# Terra_Spray.net
KiCad netlist of a schematic drawn in Altium Designer
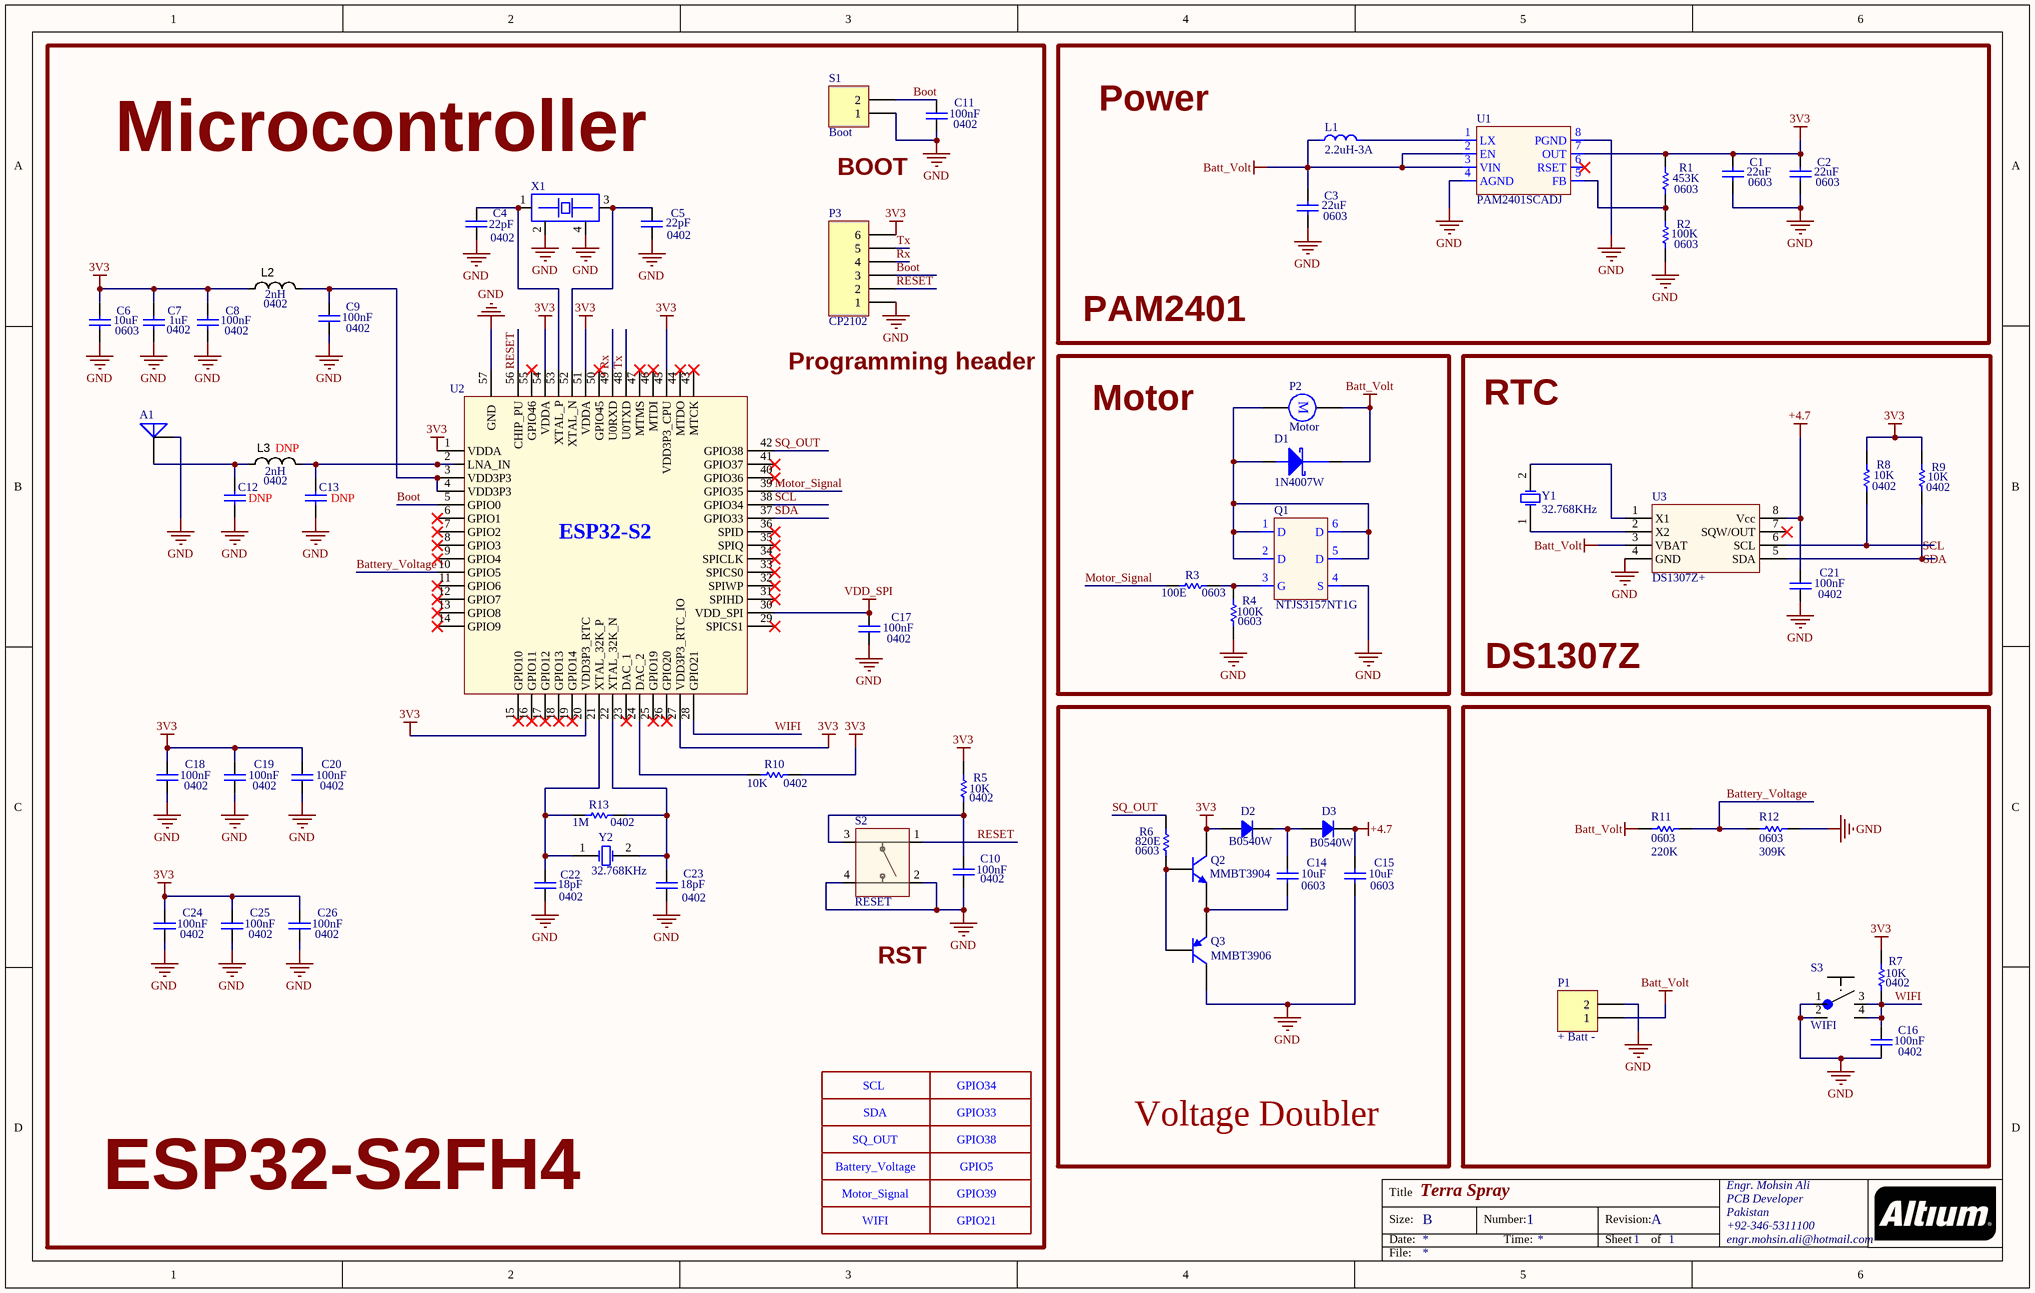
[diagram p0: Terra_Spray.SchDoc]

(export (version "E")
  (design (tool "Eeschema 10.0.6"))
  (components
    (comp (ref "A1")
      (value "Antenna_1")
      (footprint "ESP32 ANT")
      (description "PCB Antenna")
      (fields (field (name "PUBLISHER") "Altium Limited"))
      (libsource (lib "Pd's Sch Lib") (part "Antenna_1"))
    )
    (comp (ref "C1")
      (value "22uF")
      (footprint "CAPC0603")
      (description "Ceramic Capacitor,22uF,0603,6.3V")
      (fields (field (name "CASE/PACKAGE") "0603") (field (name "Comment") "Capacitor"))
      (libsource (lib "Pd's Sch Lib") (part "Capacitor"))
    )
    (comp (ref "C2")
      (value "22uF")
      (footprint "CAPC0603")
      (description "Ceramic Capacitor,22uF,0603,6.3V")
      (fields (field (name "CASE/PACKAGE") "0603") (field (name "Comment") "Capacitor"))
      (libsource (lib "Pd's Sch Lib") (part "Capacitor"))
    )
    (comp (ref "C3")
      (value "22uF")
      (footprint "CAPC0603")
      (description "Ceramic Capacitor,22uF,0603,6.3V")
      (fields (field (name "CASE/PACKAGE") "0603") (field (name "Comment") "Capacitor"))
      (libsource (lib "Pd's Sch Lib") (part "Capacitor"))
    )
    (comp (ref "C4")
      (value "22pF")
      (footprint "capc0402")
      (description "Ceramic Capacitor,22pF,0402,50V")
      (fields (field (name "CASE/PACKAGE") "0402") (field (name "Comment") "Cap"))
      (libsource (lib "CUSTOM TNY290PG") (part "Cap"))
    )
    (comp (ref "C5")
      (value "22pF")
      (footprint "capc0402")
      (description "Ceramic Capacitor,22pF,0402,50V")
      (fields (field (name "CASE/PACKAGE") "0402") (field (name "Comment") "Cap"))
      (libsource (lib "CUSTOM TNY290PG") (part "Cap"))
    )
    (comp (ref "C6")
      (value "10uF")
      (footprint "CAPC0603")
      (description "Ceramic Capacitor,10uF,0603,10V")
      (fields (field (name "CASE/PACKAGE") "0603") (field (name "Comment") "Capacitor"))
      (libsource (lib "Pd's Sch Lib") (part "Capacitor"))
    )
    (comp (ref "C7")
      (value "1uF")
      (footprint "CAPC0402")
      (description "Ceramic Capacitor,1uF,0402,6.3V")
      (fields (field (name "CASE/PACKAGE") "0402") (field (name "Comment") "Capacitor"))
      (libsource (lib "Pd's Sch Lib") (part "Capacitor"))
    )
    (comp (ref "C8")
      (value "100nF")
      (footprint "CAPC0402")
      (description "Ceramic Capacitor,100nF,0402,6.3V")
      (fields (field (name "CASE/PACKAGE") "0402") (field (name "Comment") "Cap"))
      (libsource (lib "Pd's Sch Lib") (part "Capacitor"))
    )
    (comp (ref "C9")
      (value "100nF")
      (footprint "CAPC0402")
      (description "Ceramic Capacitor,100nF,0402,6.3V")
      (fields (field (name "CASE/PACKAGE") "0402") (field (name "Comment") "Cap"))
      (libsource (lib "CUSTOM TNY290PG") (part "Cap"))
    )
    (comp (ref "C10")
      (value "100nF")
      (footprint "CAPC0402")
      (description "Ceramic Capacitor,100nF,0402,6.3V")
      (fields (field (name "CASE/PACKAGE") "0402") (field (name "Comment") "Cap"))
      (libsource (lib "CUSTOM TNY290PG") (part "Cap"))
    )
    (comp (ref "C11")
      (value "100nF")
      (footprint "CAPC0402")
      (description "Ceramic Capacitor,100nF,0402,16V")
      (fields (field (name "CASE/PACKAGE") "0402") (field (name "Comment") "Cap"))
      (libsource (lib "CUSTOM TNY290PG") (part "Cap"))
    )
    (comp (ref "C12")
      (value "Capacitor")
      (footprint "CAPC0402")
      (libsource (lib "Pd's Sch Lib") (part "Capacitor"))
    )
    (comp (ref "C13")
      (value "Capacitor")
      (footprint "CAPC0402")
      (libsource (lib "Pd's Sch Lib") (part "Capacitor"))
    )
    (comp (ref "C14")
      (value "10uF")
      (footprint "CAPC0603")
      (description "Ceramic Capacitor,10uF,0603,10V")
      (fields (field (name "CASE/PACKAGE") "0603") (field (name "Comment") "Capacitor"))
      (libsource (lib "") (part "Capacitor_1"))
    )
    (comp (ref "C15")
      (value "10uF")
      (footprint "CAPC0603")
      (description "Ceramic Capacitor,10uF,0603,10V")
      (fields (field (name "CASE/PACKAGE") "0603") (field (name "Comment") "Capacitor"))
      (libsource (lib "") (part "Capacitor_1"))
    )
    (comp (ref "C16")
      (value "100nF")
      (footprint "CAPC0402")
      (description "Ceramic Capacitor,100nF,0402,6.3\r\nV")
      (fields (field (name "CASE/PACKAGE") "0402") (field (name "Comment") "Cap"))
      (libsource (lib "CUSTOM TNY290PG") (part "Cap"))
    )
    (comp (ref "C17")
      (value "100nF")
      (footprint "CAPC0402")
      (description "Ceramic Capacitor,100nF,0402,6.3V")
      (fields (field (name "CASE/PACKAGE") "0402") (field (name "Comment") "Cap"))
      (libsource (lib "CUSTOM TNY290PG") (part "Cap"))
    )
    (comp (ref "C18")
      (value "100nF")
      (footprint "CAPC0402")
      (description "Ceramic Capacitor,100nF,0402,6.3V")
      (fields (field (name "CASE/PACKAGE") "0402") (field (name "Comment") "Cap"))
      (libsource (lib "CUSTOM TNY290PG") (part "Cap"))
    )
    (comp (ref "C19")
      (value "100nF")
      (footprint "CAPC0402")
      (description "Ceramic Capacitor,100nF,0402,6.3V")
      (fields (field (name "CASE/PACKAGE") "0402") (field (name "Comment") "Cap"))
      (libsource (lib "CUSTOM TNY290PG") (part "Cap"))
    )
    (comp (ref "C20")
      (value "100nF")
      (footprint "CAPC0402")
      (description "Ceramic Capacitor,100nF,0402,6.3V")
      (fields (field (name "CASE/PACKAGE") "0402") (field (name "Comment") "Cap"))
      (libsource (lib "CUSTOM TNY290PG") (part "Cap"))
    )
    (comp (ref "C21")
      (value "100nF")
      (footprint "CAPC0402")
      (description "Ceramic Capacitor,100nF,0402,6.3\r\nV")
      (fields (field (name "CASE/PACKAGE") "0402") (field (name "Comment") "Cap"))
      (libsource (lib "CUSTOM TNY290PG") (part "Cap"))
    )
    (comp (ref "C22")
      (value "18pF")
      (footprint "capc0402")
      (description "Ceramic Capacitor,18pF,0402,50V")
      (fields (field (name "CASE/PACKAGE") "0402") (field (name "Comment") "Cap"))
      (libsource (lib "CUSTOM TNY290PG") (part "Cap"))
    )
    (comp (ref "C23")
      (value "18pF")
      (footprint "capc0402")
      (description "Ceramic Capacitor,18pF,0402,50V")
      (fields (field (name "CASE/PACKAGE") "0402") (field (name "Comment") "Cap"))
      (libsource (lib "CUSTOM TNY290PG") (part "Cap"))
    )
    (comp (ref "C24")
      (value "100nF")
      (footprint "CAPC0402")
      (description "Ceramic Capacitor,100nF,0402,6.3V")
      (fields (field (name "CASE/PACKAGE") "0402") (field (name "Comment") "Cap"))
      (libsource (lib "CUSTOM TNY290PG") (part "Cap"))
    )
    (comp (ref "C25")
      (value "100nF")
      (footprint "CAPC0402")
      (description "Ceramic Capacitor,100nF,0402,6.3V")
      (fields (field (name "CASE/PACKAGE") "0402") (field (name "Comment") "Cap"))
      (libsource (lib "CUSTOM TNY290PG") (part "Cap"))
    )
    (comp (ref "C26")
      (value "100nF")
      (footprint "CAPC0402")
      (description "Ceramic Capacitor,100nF,0402,6.3V")
      (fields (field (name "CASE/PACKAGE") "0402") (field (name "Comment") "Cap"))
      (libsource (lib "CUSTOM TNY290PG") (part "Cap"))
    )
    (comp (ref "D1")
      (value "1N4007W")
      (footprint "SOD-123")
      (description "Rectifiers RECTIFIER DIODE 1A 1000V")
      (fields (field (name "PART NO") "CGRM4007-G"))
      (libsource (lib "Integrated_Library_FEDEVEL_APR_2015") (part "BAT54HT1G"))
    )
    (comp (ref "D2")
      (value "B0540W")
      (footprint "SOD123 - duplicate")
      (description "Diode Schottky 40V 0.5A 2-Pin SOD-123 T/R")
      (libsource (lib "Pd's Sch Lib") (part "Diode"))
    )
    (comp (ref "D3")
      (value "B0540W")
      (footprint "SOD123 - duplicate")
      (description "Diode Schottky 40V 0.5A 2-Pin SOD-123 T/R")
      (libsource (lib "Pd's Sch Lib") (part "Diode"))
    )
    (comp (ref "L1")
      (value "2.2uH-3A")
      (footprint "INDP5050X20N")
      (fields (field (name "TOLERANCE") "30%") (field (name "Comment") "Inductor"))
      (libsource (lib "Inductors") (part "74404052022"))
    )
    (comp (ref "L2")
      (value "Inductor")
      (footprint "inductor 0402")
      (description "2nH ±0.3nH 900mA 120mΩ 0402 Inductors (SMD) RoHS")
      (fields
        (field (name "MANUFACTURER PART NUMBER") "LQG15HN2N0S02D")
        (field (name "CASE/PACKAGE") "0402")
        (field (name "INDUCTANCE") "2nH")
      )
      (libsource (lib "Pd's Sch Lib") (part "Inductor"))
    )
    (comp (ref "L3")
      (value "Inductor")
      (footprint "inductor 0402")
      (description "2nH ±0.3nH 900mA 120mΩ 0402 Inductors (SMD) RoHS")
      (fields
        (field (name "MANUFACTURER PART NUMBER") "LQG15HN2N0S02D")
        (field (name "CASE CODE (IMPERIAL)") "0402")
        (field (name "INDUCTANCE") "2nH")
      )
      (libsource (lib "Pd's Sch Lib") (part "Inductor"))
    )
    (comp (ref "P1")
      (value "+ Batt -")
      (footprint "2 pin 2.5mm - Header")
      (description "Header, 2-Pin")
      (fields (field (name "PUBLISHER") "Altium Limited"))
      (libsource (lib "Miscellaneous Connectors") (part "Header 2"))
    )
    (comp (ref "P2")
      (value "Motor")
      (footprint "2 pin 2.5mm - Header")
      (description "Motor, General Kind")
      (fields (field (name "PUBLISHER") "Altium Limited"))
      (libsource (lib "Miscellaneous Devices") (part "Motor"))
    )
    (comp (ref "P3")
      (value "CP2102")
      (footprint "Header 6x1")
      (description "Header, 6-Pin")
      (fields (field (name "PUBLISHER") "Altium Limited"))
      (libsource (lib "Miscellaneous Connectors") (part "Header 6"))
    )
    (comp (ref "Q1")
      (value "Mosfet")
      (footprint "SOT-363")
      (description "N-Channel 20V 3.2A (Ta) 1W (Ta) Surface Mount SC-88/SC70-6/SOT-363")
      (fields (field (name "PART NO") "NTJS3157NT1G"))
      (libsource (lib "Terra_Spray") (part "NTJS3157NT1G"))
    )
    (comp (ref "Q2")
      (value "NPN BJT Transistor")
      (footprint "SOT-23")
      (description "Bipolar Transistors - BJT SOT-23 NPN")
      (fields (field (name "MANUFACTURER PART NUMBER") "MMBT3904"))
      (libsource (lib "Pd's Sch Lib") (part "NPN BJT Transistor"))
    )
    (comp (ref "Q3")
      (value "PNP BJT Transistor")
      (footprint "SOT-23")
      (fields
        (field (name "MANUFACTURER") "ON Semiconductor")
        (field (name "MANUFACTURER PART NUMBER") "MMBT3906")
      )
      (libsource (lib "Pd's Sch Lib") (part "PNP BJT Transistor"))
    )
    (comp (ref "R1")
      (value "453K")
      (footprint "RESC0603")
      (description "Thick Film Resistor -  453Kohm, 1%, 0603")
      (fields (field (name "CASE/PACKAGE") "0603") (field (name "Comment") "Resistor"))
      (libsource (lib "Pd's Sch Lib") (part "Resistor"))
    )
    (comp (ref "R2")
      (value "100K")
      (footprint "RESC0603")
      (description "Thick Film Resistor -  100Kohm, 1%, 0603")
      (fields (field (name "CASE/PACKAGE") "0603") (field (name "Comment") "Resistor"))
      (libsource (lib "Pd's Sch Lib") (part "Resistor"))
    )
    (comp (ref "R3")
      (value "100E")
      (footprint "RESC0603")
      (description "Thick Film Resistor -  100ohm, 1%, 0603")
      (fields (field (name "CASE/PACKAGE") "0603") (field (name "Comment") "Resistor"))
      (libsource (lib "Pd's Sch Lib") (part "Resistor"))
    )
    (comp (ref "R4")
      (value "100K")
      (footprint "RESC0603")
      (description "Thick Film Resistor -  100Kohm, 1%, 0603")
      (fields (field (name "CASE/PACKAGE") "0603") (field (name "Comment") "Resistor"))
      (libsource (lib "Pd's Sch Lib") (part "Resistor"))
    )
    (comp (ref "R5")
      (value "10K")
      (footprint "RESC0402")
      (description "Thick Film Resistor -  10Kohm, 1%, 0402")
      (fields (field (name "CASE/PACKAGE") "0402") (field (name "Comment") "Resistor"))
      (libsource (lib "Pd's Sch Lib") (part "Resistor"))
    )
    (comp (ref "R6")
      (value "820E")
      (footprint "RESC0603")
      (description "Thick Film Resistor -  820ohm, 1%, 0603")
      (fields (field (name "CASE/PACKAGE") "0603") (field (name "Comment") "Resistor"))
      (libsource (lib "Pd's Sch Lib") (part "Resistor"))
    )
    (comp (ref "R7")
      (value "10K")
      (footprint "RESC0402")
      (description "Thick Film Resistor -  10Kohm, 1%, 0402")
      (fields (field (name "CASE/PACKAGE") "0402") (field (name "Comment") "Resistor"))
      (libsource (lib "Pd's Sch Lib") (part "Resistor"))
    )
    (comp (ref "R8")
      (value "10K")
      (footprint "RESC0402")
      (description "Thick Film Resistor -  10Kohm, 1%, 0402")
      (fields (field (name "CASE/PACKAGE") "0402") (field (name "Comment") "Resistor"))
      (libsource (lib "Pd's Sch Lib") (part "Resistor"))
    )
    (comp (ref "R9")
      (value "10K")
      (footprint "RESC0402")
      (description "Thick Film Resistor -  10Kohm, 1%, 0402")
      (fields (field (name "CASE/PACKAGE") "0402") (field (name "Comment") "Resistor"))
      (libsource (lib "Pd's Sch Lib") (part "Resistor"))
    )
    (comp (ref "R10")
      (value "10K")
      (footprint "RESC0402")
      (description "Thick Film Resistor -  10Kohm, 1%, 0402")
      (fields (field (name "CASE/PACKAGE") "0402") (field (name "Comment") "Resistor"))
      (libsource (lib "Pd's Sch Lib") (part "Resistor"))
    )
    (comp (ref "R11")
      (value "220K")
      (footprint "RESC0603")
      (description "Thick Film Resistor -  220Kohm, 1%, 0603")
      (fields (field (name "CASE/PACKAGE") "0603") (field (name "Comment") "Resistor"))
      (libsource (lib "Pd's Sch Lib") (part "Resistor"))
    )
    (comp (ref "R12")
      (value "309K")
      (footprint "RESC0603")
      (description "Thick Film Resistor -  309Kohm, 1%, 0603")
      (fields (field (name "CASE/PACKAGE") "0603") (field (name "Comment") "Resistor"))
      (libsource (lib "Pd's Sch Lib") (part "Resistor"))
    )
    (comp (ref "R13")
      (value "1M")
      (footprint "RESC0402")
      (description "Thick Film Resistor -  1Mohm, 1%, 0402")
      (fields (field (name "CASE/PACKAGE") "0402") (field (name "Comment") "Resistor"))
      (libsource (lib "Pd's Sch Lib") (part "Resistor"))
    )
    (comp (ref "S1")
      (value "Boot")
      (footprint "Switch Replacement")
      (description "Header, 2-Pin")
      (fields (field (name "PUBLISHER") "Altium Limited"))
      (libsource (lib "Miscellaneous Connectors") (part "Header 2"))
    )
    (comp (ref "S2")
      (value "RESET")
      (footprint "434153017835")
      (description "SWITCH TACTILE SPST-NO 0.05A 12V")
      (fields (field (name "MANUFACTURER") "Wurth Electronics") (field (name "Comment") "Button"))
      (libsource (lib "Buttons") (part "434153017835"))
    )
    (comp (ref "S3")
      (value "WIFI")
      (footprint "FSMJ - SMD - Wifi")
      (description "Pushbutton 6x6mm, Actuator Height off PCB, Vertical 9.50mm")
      (fields (field (name "MF") "TE Connectivity") (field (name "MP") "FSM14J"))
      (libsource (lib "Main_PCB") (part "FSM14J"))
    )
    (comp (ref "U1")
      (value "PAM2401SCADJ")
      (footprint "8-TSSOP, 8-MSOP")
      (description "IC REG BOOST ADJ 3A SYNC 8MSOP")
      (libsource (lib "Regulators") (part "PAM2401SCADJ"))
    )
    (comp (ref "U2")
      (value "ESP32-S2")
      (footprint "QFN56-7x7mm")
      (description "WiFi 802.11b/g/n Transceiver Module 2.4GHz")
      (fields (field (name "MANUFACTURER PART NUMBER") "ESP32-S2FH4"))
      (libsource (lib "Pd's Sch Lib") (part "ESP32-S2"))
    )
    (comp (ref "U3")
      (value "DS1307Z+")
      (footprint "SOIC-8")
      (description "SERIAL TIME CHIP 8PIN, SOIC")
      (fields (field (name "VOLTAGE") "5V"))
      (libsource (lib "IC's") (part "DS1307Z+"))
    )
    (comp (ref "X1")
      (value "CRYSTAL_1")
      (footprint "Crystal_3225")
      (description "40MHz ±10ppm 10pF 30Ω SMD-3225 SMD Crystal Resonators RoHS")
      (fields (field (name "MANUFACTURER PART NUMBER") "7M40000049"))
      (libsource (lib "Pd's Sch Lib") (part "CRYSTAL_1_1"))
    )
    (comp (ref "Y1")
      (value "32.768KHz")
      (footprint "32.728Khz")
      (description "Crystal Oscillator")
      (fields (field (name "PUBLISHER") "Altium Limited"))
      (libsource (lib "Miscellaneous Devices") (part "XTAL"))
    )
    (comp (ref "Y2")
      (value "32.768KHz")
      (footprint "32.728Khz")
      (description "Crystal Oscillator")
      (fields (field (name "PUBLISHER") "Altium Limited"))
      (libsource (lib "Miscellaneous Devices") (part "XTAL"))
    )
  )
  (nets
    (net (code "1") (name "+4.7") (class "Default")
      (node (ref "C15") (pin "1") (pinfunction "1_1") (pintype "passive"))
      (node (ref "C21") (pin "1") (pinfunction "1_1") (pintype "passive"))
      (node (ref "D3") (pin "K") (pinfunction "K_K") (pintype "passive"))
      (node (ref "U3") (pin "8") (pinfunction "Vcc_8") (pintype "passive"))
    )
    (net (code "2") (name "/Battery_Voltage") (class "Default")
      (node (ref "R11") (pin "1") (pinfunction "1_1") (pintype "passive"))
      (node (ref "R12") (pin "2") (pinfunction "2_2") (pintype "passive"))
      (node (ref "U2") (pin "10") (pinfunction "GPIO5_10") (pintype "passive"))
    )
    (net (code "3") (name "/Boot") (class "Default")
      (node (ref "C11") (pin "2") (pinfunction "2_2") (pintype "passive"))
      (node (ref "P3") (pin "3") (pinfunction "3_3") (pintype "passive"))
      (node (ref "S1") (pin "2") (pinfunction "2_2") (pintype "passive"))
      (node (ref "U2") (pin "5") (pinfunction "GPIO0_5") (pintype "passive"))
    )
    (net (code "10") (name "/Motor_Signal") (class "Default")
      (node (ref "R3") (pin "2") (pinfunction "2_2") (pintype "passive"))
      (node (ref "U2") (pin "39") (pinfunction "GPIO35_39") (pintype "passive"))
    )
    (net (code "11") (name "/RESET") (class "Default")
      (node (ref "P3") (pin "2") (pinfunction "2_2") (pintype "passive"))
      (node (ref "S2") (pin "1") (pinfunction "1_1") (pintype "passive"))
      (node (ref "U2") (pin "56") (pinfunction "CHIP_PU_56") (pintype "passive"))
    )
    (net (code "12") (name "/Rx") (class "Default")
      (node (ref "P3") (pin "4") (pinfunction "4_4") (pintype "passive"))
      (node (ref "U2") (pin "49") (pinfunction "U0RXD_49") (pintype "passive"))
    )
    (net (code "13") (name "/SCL") (class "Default")
      (node (ref "R8") (pin "1") (pinfunction "1_1") (pintype "passive"))
      (node (ref "U2") (pin "38") (pinfunction "GPIO34_38") (pintype "passive"))
      (node (ref "U3") (pin "6") (pinfunction "SCL_6") (pintype "passive"))
    )
    (net (code "14") (name "/SDA") (class "Default")
      (node (ref "R9") (pin "1") (pinfunction "1_1") (pintype "passive"))
      (node (ref "U2") (pin "37") (pinfunction "GPIO33_37") (pintype "passive"))
      (node (ref "U3") (pin "5") (pinfunction "SDA_5") (pintype "passive"))
    )
    (net (code "15") (name "/SQ_OUT") (class "Default")
      (node (ref "R6") (pin "2") (pinfunction "2_2") (pintype "passive"))
      (node (ref "U2") (pin "42") (pinfunction "GPIO38_42") (pintype "passive"))
    )
    (net (code "16") (name "/Tx") (class "Default")
      (node (ref "P3") (pin "5") (pinfunction "5_5") (pintype "passive"))
      (node (ref "U2") (pin "48") (pinfunction "U0TXD_48") (pintype "passive"))
    )
    (net (code "17") (name "/WIFI") (class "Default")
      (node (ref "C16") (pin "2") (pinfunction "2_2") (pintype "passive"))
      (node (ref "R7") (pin "1") (pinfunction "1_1") (pintype "passive"))
      (node (ref "S3") (pin "3") (pinfunction "2_3") (pintype "passive"))
      (node (ref "S3") (pin "4") (pinfunction "2_4") (pintype "passive"))
      (node (ref "U2") (pin "28") (pinfunction "GPIO21_28") (pintype "passive"))
    )
    (net (code "18") (name "3V3") (class "Default")
      (node (ref "C1") (pin "2") (pinfunction "2_2") (pintype "passive"))
      (node (ref "C18") (pin "1") (pinfunction "1_1") (pintype "passive"))
      (node (ref "C19") (pin "1") (pinfunction "1_1") (pintype "passive"))
      (node (ref "C2") (pin "2") (pinfunction "2_2") (pintype "passive"))
      (node (ref "C20") (pin "1") (pinfunction "1_1") (pintype "passive"))
      (node (ref "C24") (pin "1") (pinfunction "1_1") (pintype "passive"))
      (node (ref "C25") (pin "1") (pinfunction "1_1") (pintype "passive"))
      (node (ref "C26") (pin "1") (pinfunction "1_1") (pintype "passive"))
      (node (ref "C6") (pin "2") (pinfunction "2_2") (pintype "passive"))
      (node (ref "C7") (pin "2") (pinfunction "2_2") (pintype "passive"))
      (node (ref "C8") (pin "2") (pinfunction "2_2") (pintype "passive"))
      (node (ref "D2") (pin "A") (pinfunction "A_A") (pintype "passive"))
      (node (ref "L2") (pin "1") (pinfunction "1_1") (pintype "passive"))
      (node (ref "P3") (pin "6") (pinfunction "6_6") (pintype "passive"))
      (node (ref "Q2") (pin "3") (pinfunction "C_3") (pintype "passive"))
      (node (ref "R1") (pin "2") (pinfunction "2_2") (pintype "passive"))
      (node (ref "R10") (pin "1") (pinfunction "1_1") (pintype "passive"))
      (node (ref "R5") (pin "2") (pinfunction "2_2") (pintype "passive"))
      (node (ref "R7") (pin "2") (pinfunction "2_2") (pintype "passive"))
      (node (ref "R8") (pin "2") (pinfunction "2_2") (pintype "passive"))
      (node (ref "R9") (pin "2") (pinfunction "2_2") (pintype "passive"))
      (node (ref "U1") (pin "7") (pinfunction "OUT_7") (pintype "passive"))
      (node (ref "U2") (pin "1") (pinfunction "VDDA_1") (pintype "passive"))
      (node (ref "U2") (pin "20") (pinfunction "VDD3P3_RTC_20") (pintype "passive"))
      (node (ref "U2") (pin "27") (pinfunction "VDD3P3_RTC_IO_27") (pintype "passive"))
      (node (ref "U2") (pin "45") (pinfunction "VDD3P3_CPU_45") (pintype "passive"))
      (node (ref "U2") (pin "51") (pinfunction "VDDA_51") (pintype "passive"))
      (node (ref "U2") (pin "54") (pinfunction "VDDA_54") (pintype "passive"))
    )
    (net (code "19") (name "Batt_Volt") (class "Default")
      (node (ref "C3") (pin "2") (pinfunction "2_2") (pintype "passive"))
      (node (ref "D1") (pin "1") (pinfunction "Cathode_1") (pintype "passive"))
      (node (ref "L1") (pin "1") (pinfunction "1_1") (pintype "passive"))
      (node (ref "P1") (pin "1") (pinfunction "1_1") (pintype "passive"))
      (node (ref "P2") (pin "1") (pinfunction "1_1") (pintype "passive"))
      (node (ref "R11") (pin "2") (pinfunction "2_2") (pintype "passive"))
      (node (ref "U1") (pin "2") (pinfunction "EN_2") (pintype "passive"))
      (node (ref "U1") (pin "3") (pinfunction "VIN_3") (pintype "passive"))
      (node (ref "U3") (pin "3") (pinfunction "VBAT_3") (pintype "passive"))
    )
    (net (code "20") (name "GND") (class "Default")
      (node (ref "A1") (pin "2") (pinfunction "GND_2") (pintype "passive"))
      (node (ref "C1") (pin "1") (pinfunction "1_1") (pintype "passive"))
      (node (ref "C10") (pin "2") (pinfunction "2_2") (pintype "passive"))
      (node (ref "C11") (pin "1") (pinfunction "1_1") (pintype "passive"))
      (node (ref "C12") (pin "1") (pinfunction "1_1") (pintype "passive"))
      (node (ref "C13") (pin "1") (pinfunction "1_1") (pintype "passive"))
      (node (ref "C15") (pin "2") (pinfunction "2_2") (pintype "passive"))
      (node (ref "C16") (pin "1") (pinfunction "1_1") (pintype "passive"))
      (node (ref "C17") (pin "2") (pinfunction "2_2") (pintype "passive"))
      (node (ref "C18") (pin "2") (pinfunction "2_2") (pintype "passive"))
      (node (ref "C19") (pin "2") (pinfunction "2_2") (pintype "passive"))
      (node (ref "C2") (pin "1") (pinfunction "1_1") (pintype "passive"))
      (node (ref "C20") (pin "2") (pinfunction "2_2") (pintype "passive"))
      (node (ref "C21") (pin "2") (pinfunction "2_2") (pintype "passive"))
      (node (ref "C22") (pin "1") (pinfunction "1_1") (pintype "passive"))
      (node (ref "C23") (pin "1") (pinfunction "1_1") (pintype "passive"))
      (node (ref "C24") (pin "2") (pinfunction "2_2") (pintype "passive"))
      (node (ref "C25") (pin "2") (pinfunction "2_2") (pintype "passive"))
      (node (ref "C26") (pin "2") (pinfunction "2_2") (pintype "passive"))
      (node (ref "C3") (pin "1") (pinfunction "1_1") (pintype "passive"))
      (node (ref "C4") (pin "1") (pinfunction "1_1") (pintype "passive"))
      (node (ref "C5") (pin "1") (pinfunction "1_1") (pintype "passive"))
      (node (ref "C6") (pin "1") (pinfunction "1_1") (pintype "passive"))
      (node (ref "C7") (pin "1") (pinfunction "1_1") (pintype "passive"))
      (node (ref "C8") (pin "1") (pinfunction "1_1") (pintype "passive"))
      (node (ref "C9") (pin "2") (pinfunction "2_2") (pintype "passive"))
      (node (ref "P1") (pin "2") (pinfunction "2_2") (pintype "passive"))
      (node (ref "P3") (pin "1") (pinfunction "1_1") (pintype "passive"))
      (node (ref "Q1") (pin "4") (pinfunction "S_4") (pintype "passive"))
      (node (ref "Q3") (pin "3") (pinfunction "C_3") (pintype "passive"))
      (node (ref "R12") (pin "1") (pinfunction "1_1") (pintype "passive"))
      (node (ref "R2") (pin "2") (pinfunction "2_2") (pintype "passive"))
      (node (ref "R4") (pin "2") (pinfunction "2_2") (pintype "passive"))
      (node (ref "S1") (pin "1") (pinfunction "1_1") (pintype "passive"))
      (node (ref "S2") (pin "2") (pinfunction "2_2") (pintype "passive"))
      (node (ref "S2") (pin "4") (pinfunction "4_4") (pintype "passive"))
      (node (ref "S3") (pin "1") (pinfunction "1_1") (pintype "passive"))
      (node (ref "S3") (pin "2") (pinfunction "1_2") (pintype "passive"))
      (node (ref "U1") (pin "4") (pinfunction "AGND_4") (pintype "passive"))
      (node (ref "U1") (pin "8") (pinfunction "PGND_8") (pintype "passive"))
      (node (ref "U2") (pin "57") (pinfunction "GND_57") (pintype "passive"))
      (node (ref "U3") (pin "4") (pinfunction "GND_4") (pintype "passive"))
      (node (ref "X1") (pin "2") (pinfunction "2_2") (pintype "passive"))
      (node (ref "X1") (pin "4") (pinfunction "4_4") (pintype "passive"))
    )
    (net (code "21") (name "Net-(A1-ANT)") (class "Default")
      (node (ref "A1") (pin "1") (pinfunction "ANT_1") (pintype "passive"))
      (node (ref "C12") (pin "2") (pinfunction "2_2") (pintype "passive"))
      (node (ref "L3") (pin "1") (pinfunction "1_1") (pintype "passive"))
    )
    (net (code "22") (name "Net-(C9-Pad1)") (class "Default")
      (node (ref "C9") (pin "1") (pinfunction "1_1") (pintype "passive"))
      (node (ref "L2") (pin "2") (pinfunction "2_2") (pintype "passive"))
      (node (ref "U2") (pin "3") (pinfunction "VDD3P3_3") (pintype "passive"))
      (node (ref "U2") (pin "4") (pinfunction "VDD3P3_4") (pintype "passive"))
    )
    (net (code "23") (name "Net-(C10-Pad1)") (class "Default")
      (node (ref "C10") (pin "1") (pinfunction "1_1") (pintype "passive"))
      (node (ref "R5") (pin "1") (pinfunction "1_1") (pintype "passive"))
      (node (ref "S2") (pin "3") (pinfunction "3_3") (pintype "passive"))
    )
    (net (code "24") (name "Net-(C14-Pad1)") (class "Default")
      (node (ref "C14") (pin "1") (pinfunction "1_1") (pintype "passive"))
      (node (ref "D2") (pin "K") (pinfunction "K_K") (pintype "passive"))
      (node (ref "D3") (pin "A") (pinfunction "A_A") (pintype "passive"))
    )
    (net (code "25") (name "Net-(D1-Anode)") (class "Default")
      (node (ref "D1") (pin "2") (pinfunction "Anode_2") (pintype "passive"))
      (node (ref "P2") (pin "2") (pinfunction "2_2") (pintype "passive"))
      (node (ref "Q1") (pin "1") (pinfunction "D_1") (pintype "passive"))
      (node (ref "Q1") (pin "2") (pinfunction "D_2") (pintype "passive"))
      (node (ref "Q1") (pin "5") (pinfunction "D_5") (pintype "passive"))
      (node (ref "Q1") (pin "6") (pinfunction "D_6") (pintype "passive"))
    )
    (net (code "26") (name "Net-(Q1-G)") (class "Default")
      (node (ref "Q1") (pin "3") (pinfunction "G_3") (pintype "passive"))
      (node (ref "R3") (pin "1") (pinfunction "1_1") (pintype "passive"))
      (node (ref "R4") (pin "1") (pinfunction "1_1") (pintype "passive"))
    )
    (net (code "27") (name "Net-(Q2-B)") (class "Default")
      (node (ref "Q2") (pin "1") (pinfunction "B_1") (pintype "passive"))
      (node (ref "Q3") (pin "1") (pinfunction "B_1") (pintype "passive"))
      (node (ref "R6") (pin "1") (pinfunction "1_1") (pintype "passive"))
    )
    (net (code "28") (name "Net-(Q2-E)") (class "Default")
      (node (ref "C14") (pin "2") (pinfunction "2_2") (pintype "passive"))
      (node (ref "Q2") (pin "2") (pinfunction "E_2") (pintype "passive"))
      (node (ref "Q3") (pin "2") (pinfunction "E_2") (pintype "passive"))
    )
    (net (code "29") (name "Net-(U1-FB)") (class "Default")
      (node (ref "R1") (pin "1") (pinfunction "1_1") (pintype "passive"))
      (node (ref "R2") (pin "1") (pinfunction "1_1") (pintype "passive"))
      (node (ref "U1") (pin "5") (pinfunction "FB_5") (pintype "passive"))
    )
    (net (code "30") (name "Net-(U1-LX)") (class "Default")
      (node (ref "L1") (pin "2") (pinfunction "2_2") (pintype "passive"))
      (node (ref "U1") (pin "1") (pinfunction "LX_1") (pintype "passive"))
    )
    (net (code "31") (name "Net-(U2-DAC_2)") (class "Default")
      (node (ref "R10") (pin "2") (pinfunction "2_2") (pintype "passive"))
      (node (ref "U2") (pin "24") (pinfunction "DAC_2_24") (pintype "passive"))
    )
    (net (code "32") (name "Net-(U2-LNA_IN)") (class "Default")
      (node (ref "C13") (pin "2") (pinfunction "2_2") (pintype "passive"))
      (node (ref "L3") (pin "2") (pinfunction "2_2") (pintype "passive"))
      (node (ref "U2") (pin "2") (pinfunction "LNA_IN_2") (pintype "passive"))
    )
    (net (code "33") (name "Net-(U2-XTAL_32K_N)") (class "Default")
      (node (ref "C23") (pin "2") (pinfunction "2_2") (pintype "passive"))
      (node (ref "R13") (pin "2") (pinfunction "2_2") (pintype "passive"))
      (node (ref "U2") (pin "22") (pinfunction "XTAL_32K_N_22") (pintype "passive"))
      (node (ref "Y2") (pin "2") (pinfunction "OSC2_2") (pintype "passive"))
    )
    (net (code "34") (name "Net-(U2-XTAL_32K_P)") (class "Default")
      (node (ref "C22") (pin "2") (pinfunction "2_2") (pintype "passive"))
      (node (ref "R13") (pin "1") (pinfunction "1_1") (pintype "passive"))
      (node (ref "U2") (pin "21") (pinfunction "XTAL_32K_P_21") (pintype "passive"))
      (node (ref "Y2") (pin "1") (pinfunction "OSC1_1") (pintype "passive"))
    )
    (net (code "35") (name "Net-(U2-XTAL_N)") (class "Default")
      (node (ref "C5") (pin "2") (pinfunction "2_2") (pintype "passive"))
      (node (ref "U2") (pin "52") (pinfunction "XTAL_N_52") (pintype "passive"))
      (node (ref "X1") (pin "3") (pinfunction "3_3") (pintype "passive"))
    )
    (net (code "36") (name "Net-(U2-XTAL_P)") (class "Default")
      (node (ref "C4") (pin "2") (pinfunction "2_2") (pintype "passive"))
      (node (ref "U2") (pin "53") (pinfunction "XTAL_P_53") (pintype "passive"))
      (node (ref "X1") (pin "1") (pinfunction "1_1") (pintype "passive"))
    )
    (net (code "37") (name "Net-(U3-X1)") (class "Default")
      (node (ref "U3") (pin "1") (pinfunction "X1_1") (pintype "passive"))
      (node (ref "Y1") (pin "2") (pinfunction "OSC2_2") (pintype "passive"))
    )
    (net (code "38") (name "Net-(U3-X2)") (class "Default")
      (node (ref "U3") (pin "2") (pinfunction "X2_2") (pintype "passive"))
      (node (ref "Y1") (pin "1") (pinfunction "OSC1_1") (pintype "passive"))
    )
    (net (code "39") (name "VDD_SPI") (class "Default")
      (node (ref "C17") (pin "1") (pinfunction "1_1") (pintype "passive"))
      (node (ref "U2") (pin "30") (pinfunction "VDD_SPI_30") (pintype "passive"))
    )
    (net (code "40") (name "unconnected-(U1-RSET-Pad6)") (class "Default")
      (node (ref "U1") (pin "6") (pinfunction "RSET_6") (pintype "passive+no_connect"))
    )
    (net (code "41") (name "unconnected-(U2-DAC_1-Pad23)") (class "Default")
      (node (ref "U2") (pin "23") (pinfunction "DAC_1_23") (pintype "passive+no_connect"))
    )
    (net (code "42") (name "unconnected-(U2-GPIO1-Pad6)") (class "Default")
      (node (ref "U2") (pin "6") (pinfunction "GPIO1_6") (pintype "passive+no_connect"))
    )
    (net (code "43") (name "unconnected-(U2-GPIO2-Pad7)") (class "Default")
      (node (ref "U2") (pin "7") (pinfunction "GPIO2_7") (pintype "passive+no_connect"))
    )
    (net (code "44") (name "unconnected-(U2-GPIO3-Pad8)") (class "Default")
      (node (ref "U2") (pin "8") (pinfunction "GPIO3_8") (pintype "passive+no_connect"))
    )
    (net (code "45") (name "unconnected-(U2-GPIO4-Pad9)") (class "Default")
      (node (ref "U2") (pin "9") (pinfunction "GPIO4_9") (pintype "passive+no_connect"))
    )
    (net (code "46") (name "unconnected-(U2-GPIO6-Pad11)") (class "Default")
      (node (ref "U2") (pin "11") (pinfunction "GPIO6_11") (pintype "passive+no_connect"))
    )
    (net (code "47") (name "unconnected-(U2-GPIO7-Pad12)") (class "Default")
      (node (ref "U2") (pin "12") (pinfunction "GPIO7_12") (pintype "passive+no_connect"))
    )
    (net (code "48") (name "unconnected-(U2-GPIO8-Pad13)") (class "Default")
      (node (ref "U2") (pin "13") (pinfunction "GPIO8_13") (pintype "passive+no_connect"))
    )
    (net (code "49") (name "unconnected-(U2-GPIO9-Pad14)") (class "Default")
      (node (ref "U2") (pin "14") (pinfunction "GPIO9_14") (pintype "passive+no_connect"))
    )
    (net (code "50") (name "unconnected-(U2-GPIO10-Pad15)") (class "Default")
      (node (ref "U2") (pin "15") (pinfunction "GPIO10_15") (pintype "passive+no_connect"))
    )
    (net (code "51") (name "unconnected-(U2-GPIO11-Pad16)") (class "Default")
      (node (ref "U2") (pin "16") (pinfunction "GPIO11_16") (pintype "passive+no_connect"))
    )
    (net (code "52") (name "unconnected-(U2-GPIO12-Pad17)") (class "Default")
      (node (ref "U2") (pin "17") (pinfunction "GPIO12_17") (pintype "passive+no_connect"))
    )
    (net (code "53") (name "unconnected-(U2-GPIO13-Pad18)") (class "Default")
      (node (ref "U2") (pin "18") (pinfunction "GPIO13_18") (pintype "passive+no_connect"))
    )
    (net (code "54") (name "unconnected-(U2-GPIO14-Pad19)") (class "Default")
      (node (ref "U2") (pin "19") (pinfunction "GPIO14_19") (pintype "passive+no_connect"))
    )
    (net (code "55") (name "unconnected-(U2-GPIO19-Pad25)") (class "Default")
      (node (ref "U2") (pin "25") (pinfunction "GPIO19_25") (pintype "passive+no_connect"))
    )
    (net (code "56") (name "unconnected-(U2-GPIO20-Pad26)") (class "Default")
      (node (ref "U2") (pin "26") (pinfunction "GPIO20_26") (pintype "passive+no_connect"))
    )
    (net (code "57") (name "unconnected-(U2-GPIO36-Pad40)") (class "Default")
      (node (ref "U2") (pin "40") (pinfunction "GPIO36_40") (pintype "passive+no_connect"))
    )
    (net (code "58") (name "unconnected-(U2-GPIO37-Pad41)") (class "Default")
      (node (ref "U2") (pin "41") (pinfunction "GPIO37_41") (pintype "passive+no_connect"))
    )
    (net (code "59") (name "unconnected-(U2-GPIO45-Pad50)") (class "Default")
      (node (ref "U2") (pin "50") (pinfunction "GPIO45_50") (pintype "passive+no_connect"))
    )
    (net (code "60") (name "unconnected-(U2-GPIO46-Pad55)") (class "Default")
      (node (ref "U2") (pin "55") (pinfunction "GPIO46_55") (pintype "passive+no_connect"))
    )
    (net (code "61") (name "unconnected-(U2-MTCK-Pad43)") (class "Default")
      (node (ref "U2") (pin "43") (pinfunction "MTCK_43") (pintype "passive+no_connect"))
    )
    (net (code "62") (name "unconnected-(U2-MTDI-Pad46)") (class "Default")
      (node (ref "U2") (pin "46") (pinfunction "MTDI_46") (pintype "passive+no_connect"))
    )
    (net (code "63") (name "unconnected-(U2-MTDO-Pad44)") (class "Default")
      (node (ref "U2") (pin "44") (pinfunction "MTDO_44") (pintype "passive+no_connect"))
    )
    (net (code "64") (name "unconnected-(U2-MTMS-Pad47)") (class "Default")
      (node (ref "U2") (pin "47") (pinfunction "MTMS_47") (pintype "passive+no_connect"))
    )
    (net (code "65") (name "unconnected-(U2-SPICLK-Pad34)") (class "Default")
      (node (ref "U2") (pin "34") (pinfunction "SPICLK_34") (pintype "passive+no_connect"))
    )
    (net (code "66") (name "unconnected-(U2-SPICS0-Pad33)") (class "Default")
      (node (ref "U2") (pin "33") (pinfunction "SPICS0_33") (pintype "passive+no_connect"))
    )
    (net (code "67") (name "unconnected-(U2-SPICS1-Pad29)") (class "Default")
      (node (ref "U2") (pin "29") (pinfunction "SPICS1_29") (pintype "passive+no_connect"))
    )
    (net (code "68") (name "unconnected-(U2-SPID-Pad36)") (class "Default")
      (node (ref "U2") (pin "36") (pinfunction "SPID_36") (pintype "passive+no_connect"))
    )
    (net (code "69") (name "unconnected-(U2-SPIHD-Pad31)") (class "Default")
      (node (ref "U2") (pin "31") (pinfunction "SPIHD_31") (pintype "passive+no_connect"))
    )
    (net (code "70") (name "unconnected-(U2-SPIQ-Pad35)") (class "Default")
      (node (ref "U2") (pin "35") (pinfunction "SPIQ_35") (pintype "passive+no_connect"))
    )
    (net (code "71") (name "unconnected-(U2-SPIWP-Pad32)") (class "Default")
      (node (ref "U2") (pin "32") (pinfunction "SPIWP_32") (pintype "passive+no_connect"))
    )
    (net (code "72") (name "unconnected-(U3-SQW{slash}OUT-Pad7)") (class "Default")
      (node (ref "U3") (pin "7") (pinfunction "SQW/OUT_7") (pintype "passive+no_connect"))
    )
  )
)
